# atxpd.net
KiCad netlist of a schematic drawn in EAGLE
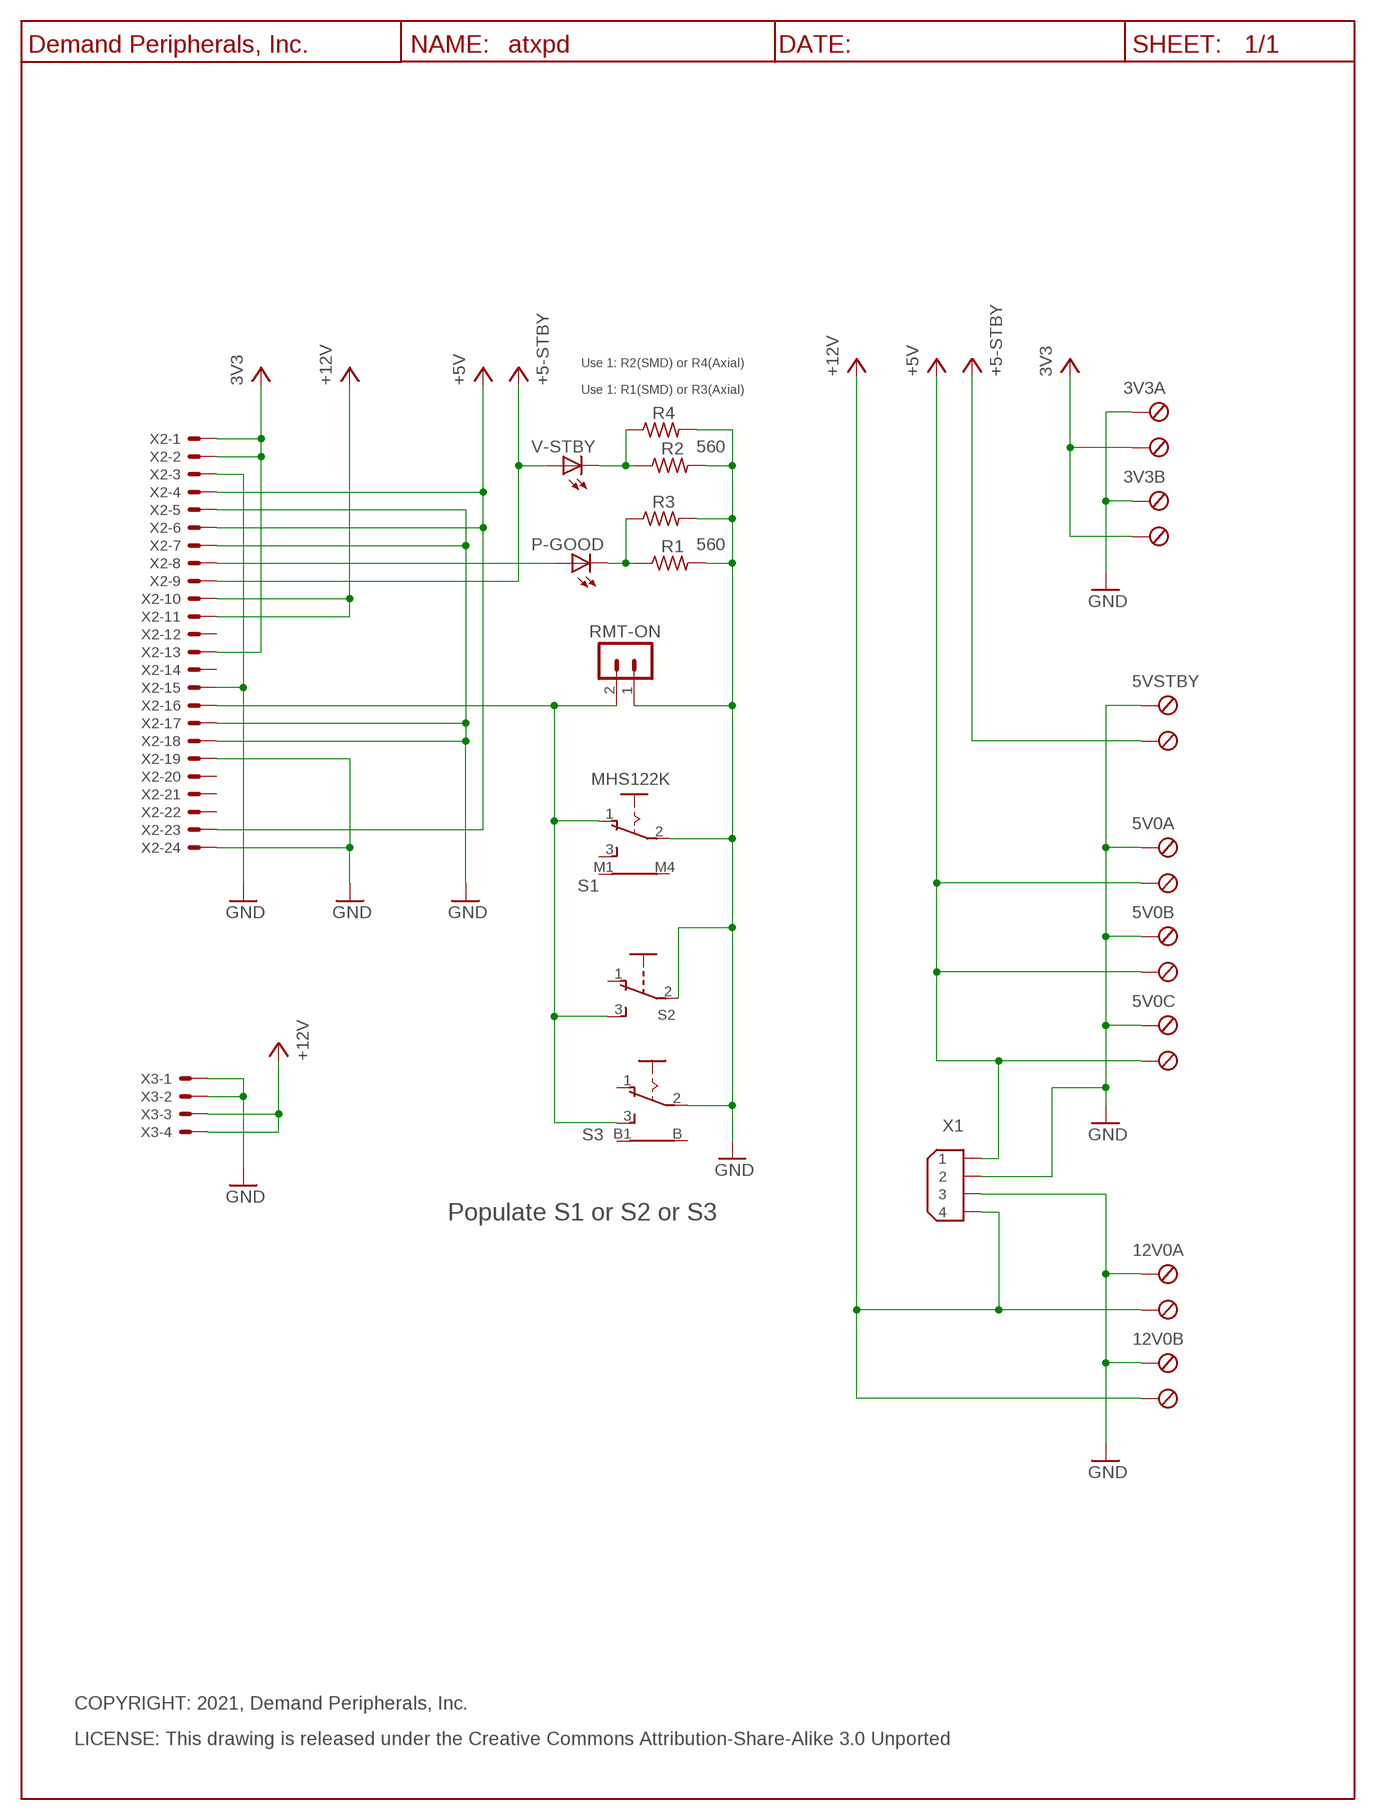
[diagram p0: schematic, sheet 1]

(export (version "E")
  (design (tool "Eeschema 10.0.6"))
  (components
    (comp (ref "3V3A")
      (value "TBLK-5.08-X2")
      (footprint "eagle-import:TBLK-5.08-X2")
      (libsource (lib "eagle-import") (part "TBLK-5.08-X2"))
    )
    (comp (ref "3V3B")
      (value "TBLK-5.08-X2")
      (footprint "eagle-import:TBLK-5.08-X2")
      (libsource (lib "eagle-import") (part "TBLK-5.08-X2"))
    )
    (comp (ref "5V0A")
      (value "TBLK-5.08-X2")
      (footprint "eagle-import:TBLK-5.08-X2")
      (libsource (lib "eagle-import") (part "TBLK-5.08-X2"))
    )
    (comp (ref "5V0B")
      (value "TBLK-5.08-X2")
      (footprint "eagle-import:TBLK-5.08-X2")
      (libsource (lib "eagle-import") (part "TBLK-5.08-X2"))
    )
    (comp (ref "5V0C")
      (value "TBLK-5.08-X2")
      (footprint "eagle-import:TBLK-5.08-X2")
      (libsource (lib "eagle-import") (part "TBLK-5.08-X2"))
    )
    (comp (ref "5VSTBY")
      (value "TBLK-5.08-X2")
      (footprint "eagle-import:TBLK-5.08-X2")
      (libsource (lib "eagle-import") (part "TBLK-5.08-X2"))
    )
    (comp (ref "12V0A")
      (value "TBLK-5.08-X2")
      (footprint "eagle-import:TBLK-5.08-X2")
      (libsource (lib "eagle-import") (part "TBLK-5.08-X2"))
    )
    (comp (ref "12V0B")
      (value "TBLK-5.08-X2")
      (footprint "eagle-import:TBLK-5.08-X2")
      (libsource (lib "eagle-import") (part "TBLK-5.08-X2"))
    )
    (comp (ref "P-GOOD")
      (value "3mm_LED")
      (footprint "eagle-import:LED5MM")
      (libsource (lib "eagle-import") (part "LED-5MM-RED"))
    )
    (comp (ref "R1")
      (value "560")
      (footprint "eagle-import:R0603")
      (libsource (lib "eagle-import") (part "R560_R0603"))
    )
    (comp (ref "R2")
      (value "560")
      (footprint "eagle-import:R0603")
      (libsource (lib "eagle-import") (part "R560_R0603"))
    )
    (comp (ref "R3")
      (value "560")
      (footprint "eagle-import:R4TENTHS")
      (libsource (lib "eagle-import") (part "R560_"))
    )
    (comp (ref "R4")
      (value "560")
      (footprint "eagle-import:R4TENTHS")
      (libsource (lib "eagle-import") (part "R560_"))
    )
    (comp (ref "RMT-ON")
      (value "PinHdr254-2")
      (footprint "eagle-import:HDR-2X1")
      (libsource (lib "eagle-import") (part "HDR-2X1-LCK"))
    )
    (comp (ref "S1")
      (value "MHS122K")
      (footprint "eagle-import:MHS122K")
      (libsource (lib "eagle-import") (part "MHS122K"))
    )
    (comp (ref "S2")
      (value "TINYTOGGLE-SPDT-TH")
      (footprint "eagle-import:SPDT-TENTHINCH")
      (libsource (lib "eagle-import") (part "TINYTOGGLE-SPDT-TH"))
    )
    (comp (ref "S3")
      (value "Vert_SW(Option)")
      (footprint "eagle-import:TOGGLE_SPDT_PC")
      (libsource (lib "eagle-import") (part "TOGGLE_SPDT_PC"))
    )
    (comp (ref "U$1")
      (value "DP_FRAME_P")
      (footprint "eagle-import:LETTER_P")
      (libsource (lib "eagle-import") (part "DP_FRAME_P"))
    )
    (comp (ref "V-STBY")
      (value "3mm_LED")
      (footprint "eagle-import:LED5MM")
      (libsource (lib "eagle-import") (part "LED-5MM-GRN"))
    )
    (comp (ref "X1")
      (value "9090-4V")
      (footprint "eagle-import:9090-4V")
      (libsource (lib "eagle-import") (part "9090-4V"))
    )
    (comp (ref "X2")
      (value "ATX_Std")
      (footprint "eagle-import:5566-24MOD")
      (libsource (lib "eagle-import") (part "5566-24MOD"))
    )
    (comp (ref "X3")
      (value "ATX_Plus4")
      (footprint "eagle-import:5566-4MOD")
      (libsource (lib "eagle-import") (part "5566-4MOD"))
    )
  )
  (nets
    (net (code "1") (name "+5-STBY") (class "Default")
      (node (ref "5VSTBY") (pin "2") (pinfunction "KL1_2") (pintype "passive"))
      (node (ref "V-STBY") (pin "A") (pinfunction "A_A") (pintype "passive"))
      (node (ref "X2") (pin "9") (pinfunction "S_9") (pintype "passive"))
    )
    (net (code "2") (name "+5V") (class "Default")
      (node (ref "5V0A") (pin "2") (pinfunction "KL1_2") (pintype "passive"))
      (node (ref "5V0B") (pin "2") (pinfunction "KL1_2") (pintype "passive"))
      (node (ref "5V0C") (pin "2") (pinfunction "KL1_2") (pintype "passive"))
      (node (ref "X1") (pin "1") (pinfunction "1_1") (pintype "passive"))
      (node (ref "X2") (pin "23") (pinfunction "S_23") (pintype "passive"))
      (node (ref "X2") (pin "4") (pinfunction "S_4") (pintype "passive"))
      (node (ref "X2") (pin "6") (pinfunction "S_6") (pintype "passive"))
    )
    (net (code "3") (name "+12V") (class "Default")
      (node (ref "12V0A") (pin "2") (pinfunction "KL1_2") (pintype "passive"))
      (node (ref "12V0B") (pin "2") (pinfunction "KL1_2") (pintype "passive"))
      (node (ref "X1") (pin "4") (pinfunction "4_4") (pintype "passive"))
      (node (ref "X2") (pin "10") (pinfunction "S_10") (pintype "passive"))
      (node (ref "X2") (pin "11") (pinfunction "S_11") (pintype "passive"))
      (node (ref "X3") (pin "3") (pinfunction "S_3") (pintype "passive"))
      (node (ref "X3") (pin "4") (pinfunction "S_4") (pintype "passive"))
    )
    (net (code "4") (name "3V3") (class "Default")
      (node (ref "3V3A") (pin "2") (pinfunction "KL1_2") (pintype "passive"))
      (node (ref "3V3B") (pin "2") (pinfunction "KL1_2") (pintype "passive"))
      (node (ref "X2") (pin "1") (pinfunction "S_1") (pintype "passive"))
      (node (ref "X2") (pin "13") (pinfunction "S_13") (pintype "passive"))
      (node (ref "X2") (pin "2") (pinfunction "S_2") (pintype "passive"))
    )
    (net (code "5") (name "GND") (class "Default")
      (node (ref "12V0A") (pin "1") (pinfunction "KL_1") (pintype "passive"))
      (node (ref "12V0B") (pin "1") (pinfunction "KL_1") (pintype "passive"))
      (node (ref "3V3A") (pin "1") (pinfunction "KL_1") (pintype "passive"))
      (node (ref "3V3B") (pin "1") (pinfunction "KL_1") (pintype "passive"))
      (node (ref "5V0A") (pin "1") (pinfunction "KL_1") (pintype "passive"))
      (node (ref "5V0B") (pin "1") (pinfunction "KL_1") (pintype "passive"))
      (node (ref "5V0C") (pin "1") (pinfunction "KL_1") (pintype "passive"))
      (node (ref "5VSTBY") (pin "1") (pinfunction "KL_1") (pintype "passive"))
      (node (ref "R1") (pin "2") (pinfunction "2_2") (pintype "passive"))
      (node (ref "R2") (pin "2") (pinfunction "2_2") (pintype "passive"))
      (node (ref "R3") (pin "2") (pinfunction "2_2") (pintype "passive"))
      (node (ref "R4") (pin "2") (pinfunction "2_2") (pintype "passive"))
      (node (ref "RMT-ON") (pin "1") (pinfunction "2_1") (pintype "passive"))
      (node (ref "S1") (pin "2") (pinfunction "P_2") (pintype "passive"))
      (node (ref "S2") (pin "2") (pinfunction "2_2") (pintype "passive"))
      (node (ref "S3") (pin "2") (pinfunction "P_2") (pintype "passive"))
      (node (ref "X1") (pin "2") (pinfunction "2_2") (pintype "passive"))
      (node (ref "X1") (pin "3") (pinfunction "3_3") (pintype "passive"))
      (node (ref "X2") (pin "15") (pinfunction "S_15") (pintype "passive"))
      (node (ref "X2") (pin "17") (pinfunction "S_17") (pintype "passive"))
      (node (ref "X2") (pin "18") (pinfunction "S_18") (pintype "passive"))
      (node (ref "X2") (pin "19") (pinfunction "S_19") (pintype "passive"))
      (node (ref "X2") (pin "24") (pinfunction "S_24") (pintype "passive"))
      (node (ref "X2") (pin "3") (pinfunction "S_3") (pintype "passive"))
      (node (ref "X2") (pin "5") (pinfunction "S_5") (pintype "passive"))
      (node (ref "X2") (pin "7") (pinfunction "S_7") (pintype "passive"))
      (node (ref "X3") (pin "1") (pinfunction "S_1") (pintype "passive"))
      (node (ref "X3") (pin "2") (pinfunction "S_2") (pintype "passive"))
    )
    (net (code "6") (name "Net-(P-GOOD-PadC)") (class "Default")
      (node (ref "P-GOOD") (pin "C") (pinfunction "C_C") (pintype "passive"))
      (node (ref "R1") (pin "1") (pinfunction "1_1") (pintype "passive"))
      (node (ref "R3") (pin "1") (pinfunction "1_1") (pintype "passive"))
    )
    (net (code "7") (name "Net-(R2-Pad1)") (class "Default")
      (node (ref "R2") (pin "1") (pinfunction "1_1") (pintype "passive"))
      (node (ref "R4") (pin "1") (pinfunction "1_1") (pintype "passive"))
      (node (ref "V-STBY") (pin "C") (pinfunction "C_C") (pintype "passive"))
    )
    (net (code "8") (name "Net-(RMT-ON-1)") (class "Default")
      (node (ref "RMT-ON") (pin "2") (pinfunction "1_2") (pintype "passive"))
      (node (ref "S1") (pin "1") (pinfunction "O_1") (pintype "passive"))
      (node (ref "S2") (pin "3") (pinfunction "3_3") (pintype "passive"))
      (node (ref "S3") (pin "3") (pinfunction "S_3") (pintype "passive"))
      (node (ref "X2") (pin "16") (pinfunction "S_16") (pintype "passive"))
    )
    (net (code "9") (name "Net-(X2W-S)") (class "Default")
      (node (ref "P-GOOD") (pin "A") (pinfunction "A_A") (pintype "passive"))
      (node (ref "X2") (pin "8") (pinfunction "S_8") (pintype "passive"))
    )
    (net (code "10") (name "unconnected-(S1-B-PadM4)") (class "Default")
      (node (ref "S1") (pin "M4") (pinfunction "B_M4") (pintype "passive"))
    )
    (net (code "11") (name "unconnected-(S1-B1-PadM1)") (class "Default")
      (node (ref "S1") (pin "M1") (pinfunction "B1_M1") (pintype "passive"))
    )
    (net (code "12") (name "unconnected-(S1-S-Pad3)") (class "Default")
      (node (ref "S1") (pin "3") (pinfunction "S_3") (pintype "passive"))
    )
    (net (code "13") (name "unconnected-(S2-Pad1)") (class "Default")
      (node (ref "S2") (pin "1") (pinfunction "1_1") (pintype "passive"))
    )
    (net (code "14") (name "unconnected-(S3-O-Pad1)") (class "Default")
      (node (ref "S3") (pin "1") (pinfunction "O_1") (pintype "passive"))
    )
    (net (code "15") (name "unconnected-(S3-PadB)") (class "Default")
      (node (ref "S3") (pin "B") (pinfunction "B_B") (pintype "passive"))
    )
    (net (code "16") (name "unconnected-(S3-PadB1)") (class "Default")
      (node (ref "S3") (pin "B1") (pinfunction "B1_B1") (pintype "passive"))
    )
    (net (code "17") (name "unconnected-(X2D-S-Pad12)") (class "Default")
      (node (ref "X2") (pin "12") (pinfunction "S_12") (pintype "passive"))
    )
    (net (code "18") (name "unconnected-(X2F-S-Pad14)") (class "Default")
      (node (ref "X2") (pin "14") (pinfunction "S_14") (pintype "passive"))
    )
    (net (code "19") (name "unconnected-(X2M-S-Pad20)") (class "Default")
      (node (ref "X2") (pin "20") (pinfunction "S_20") (pintype "passive"))
    )
    (net (code "20") (name "unconnected-(X2N-S-Pad21)") (class "Default")
      (node (ref "X2") (pin "21") (pinfunction "S_21") (pintype "passive"))
    )
    (net (code "21") (name "unconnected-(X2O-S-Pad22)") (class "Default")
      (node (ref "X2") (pin "22") (pinfunction "S_22") (pintype "passive"))
    )
  )
)
